# NODE_3_SCH.net
KiCad netlist of a schematic drawn in Altium Designer
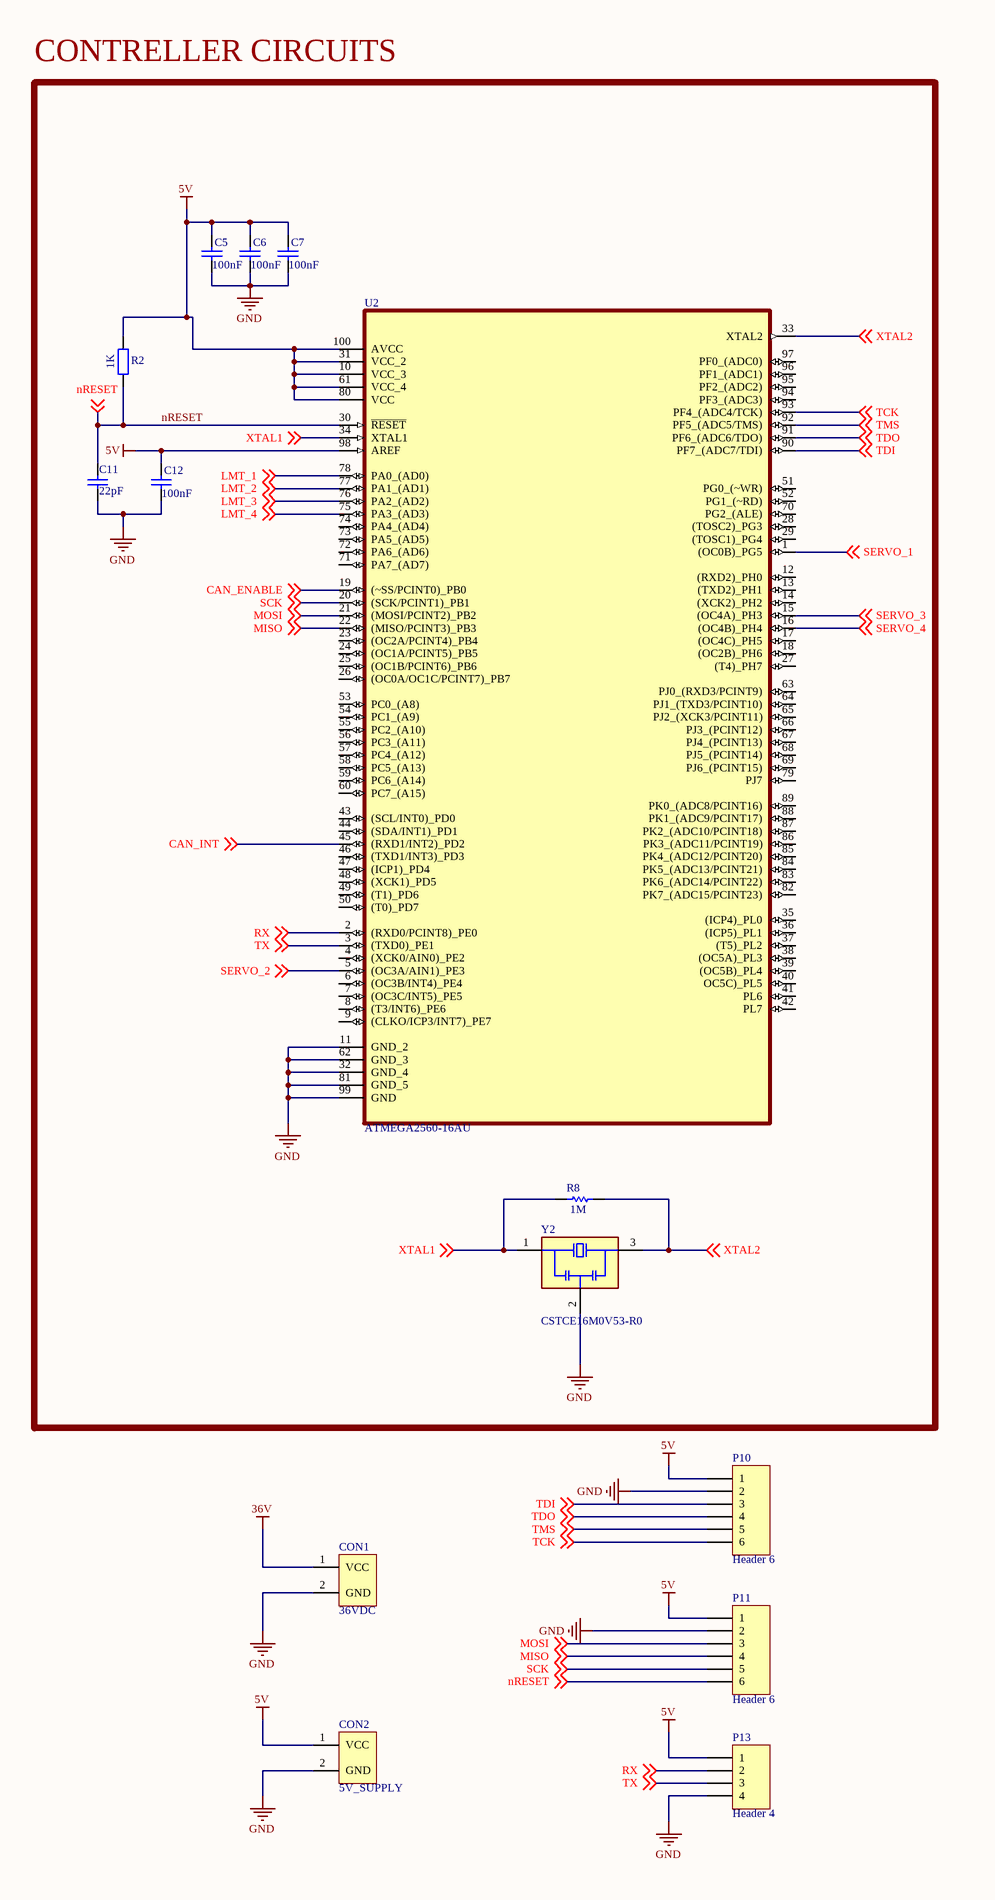
[diagram p0: NODE_3_SCH.SchDoc, left]
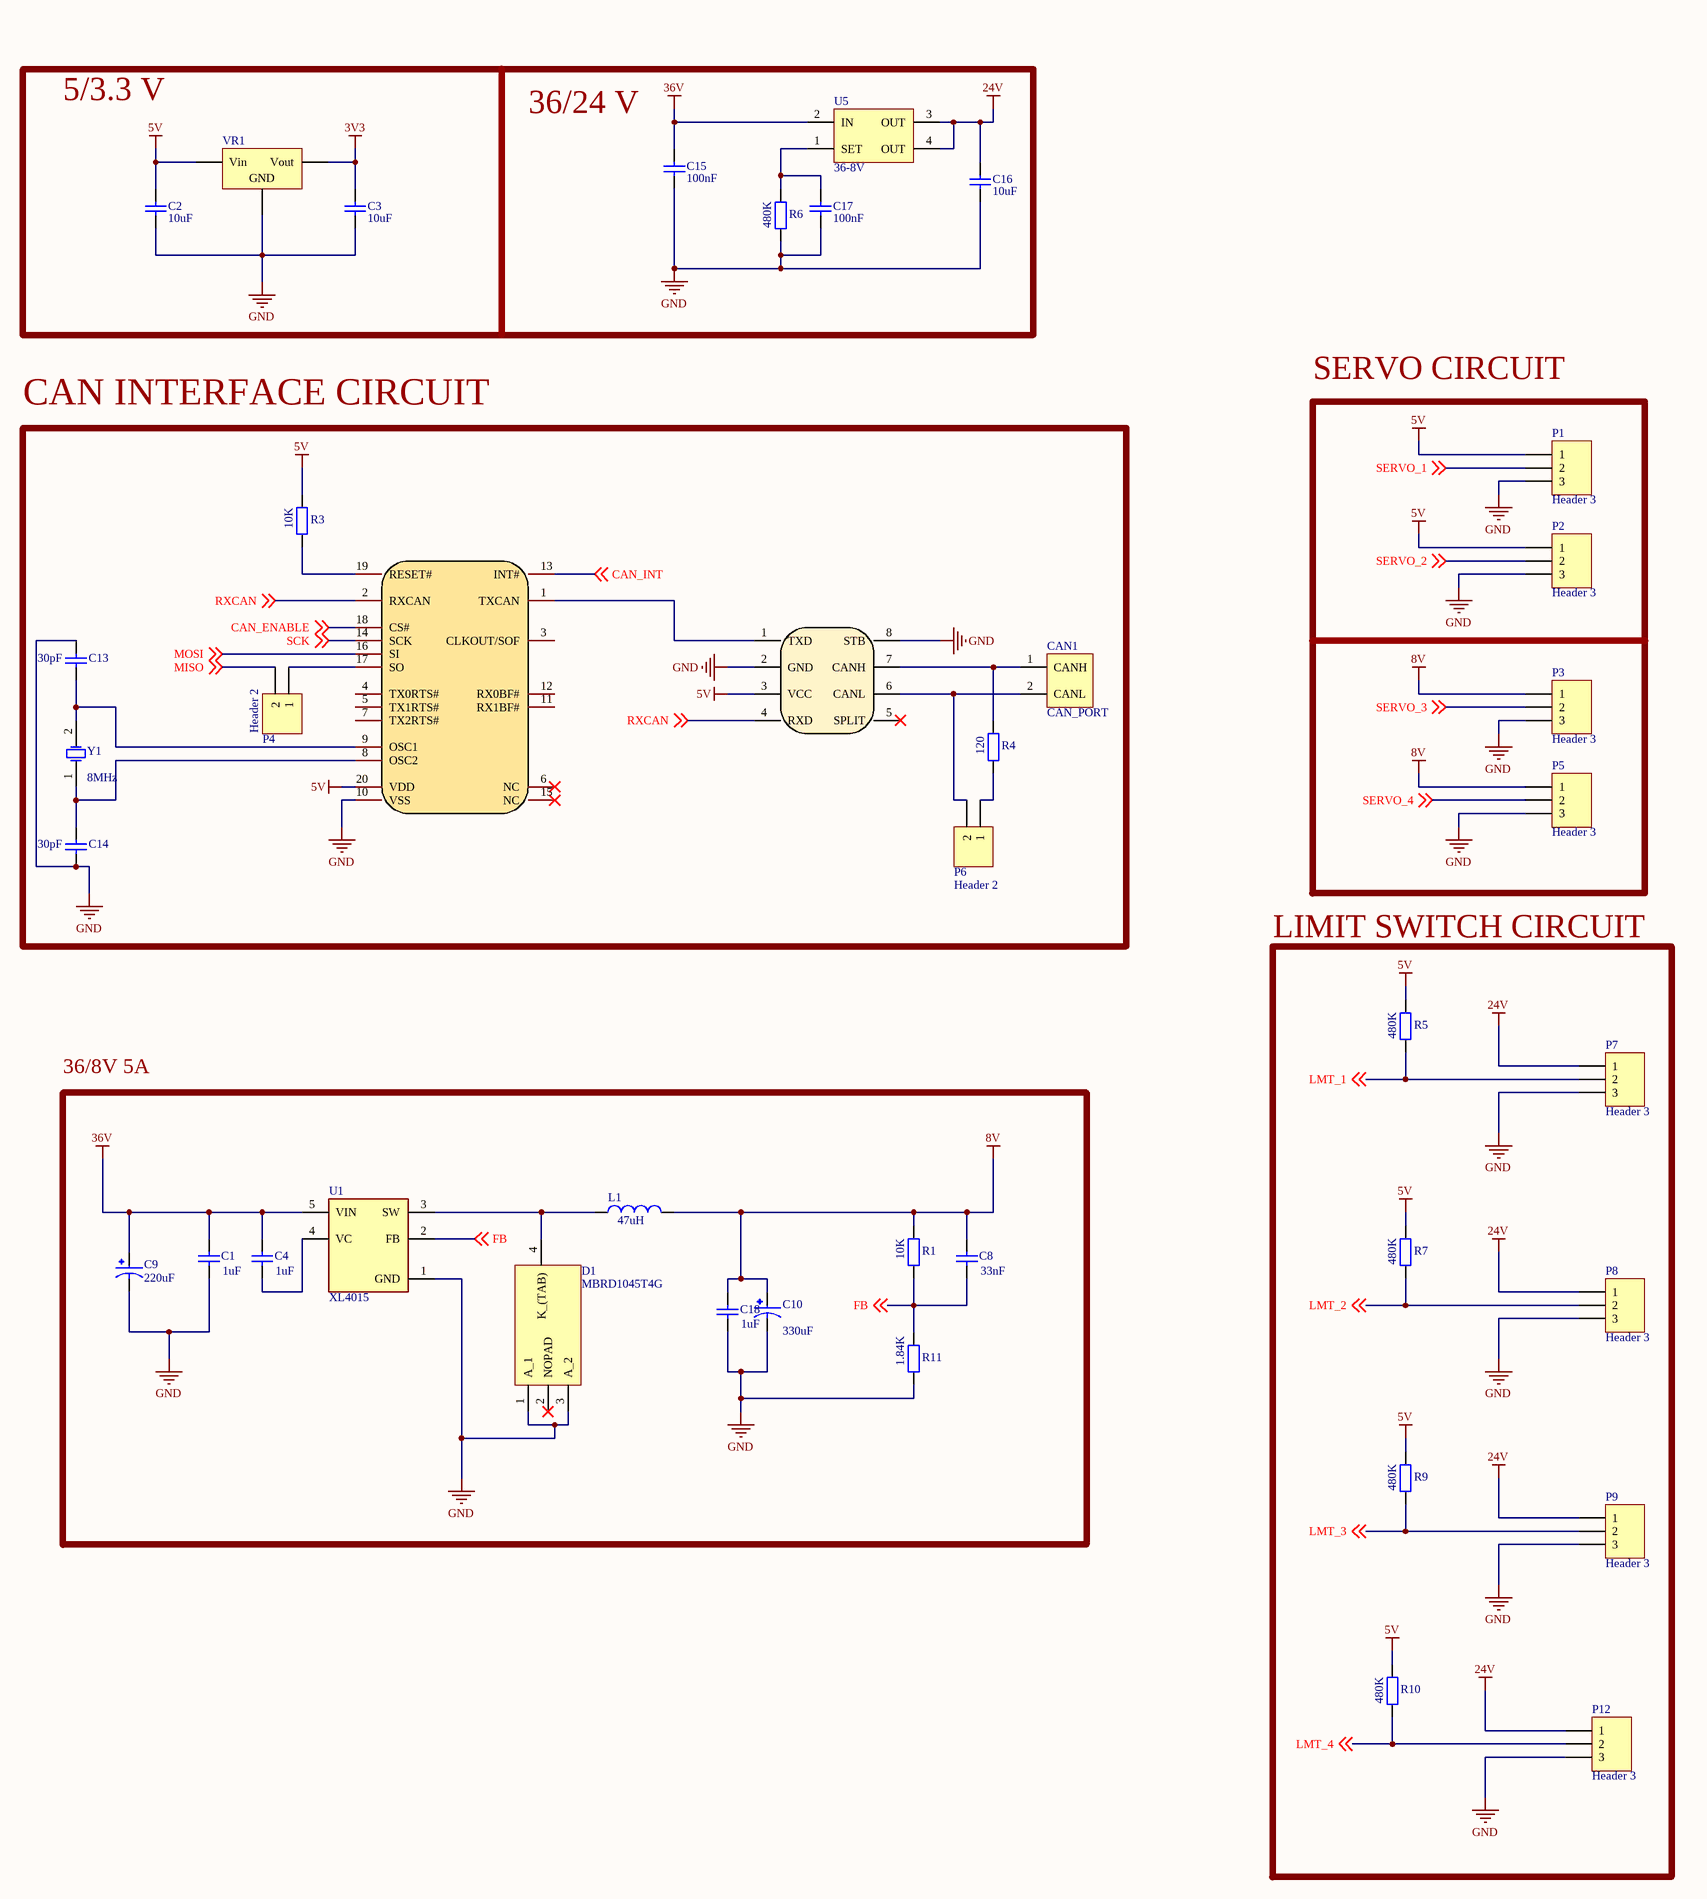
[diagram p1: NODE_3_SCH.SchDoc, right]

(export (version "E")
  (design (tool "Eeschema 10.0.6"))
  (components
    (comp (ref "C1")
      (value "1uF")
      (footprint "CAPC2012X135N")
      (description "Capacitor")
      (fields
        (field (name "PART NUMBER") "CL21B105KBFNNNE")
        (field (name "Comment") "Cap")
        (field (name "PUBLISHER") "Altium Limited")
      )
      (libsource (lib "Miscellaneous Devices") (part "Cap"))
    )
    (comp (ref "C2")
      (value "10uF")
      (footprint "CAPC2012X135N")
      (description "Capacitor")
      (fields
        (field (name "PART NUMBER") "CL21A106KOQNNNE")
        (field (name "Comment") "Cap")
        (field (name "PUBLISHER") "Altium Limited")
      )
      (libsource (lib "Miscellaneous Devices") (part "Cap"))
    )
    (comp (ref "C3")
      (value "10uF")
      (footprint "CAPC2012X135N")
      (description "Capacitor")
      (fields
        (field (name "PART NUMBER") "CL21A106KOQNNNE")
        (field (name "Comment") "Cap")
        (field (name "PUBLISHER") "Altium Limited")
      )
      (libsource (lib "Miscellaneous Devices") (part "Cap"))
    )
    (comp (ref "C4")
      (value "1uF")
      (footprint "CAPC2012X135N")
      (description "Capacitor")
      (fields
        (field (name "PART NUMBER") "CL21B105KBFNNNE")
        (field (name "Comment") "Cap")
        (field (name "PUBLISHER") "Altium Limited")
      )
      (libsource (lib "Miscellaneous Devices") (part "Cap"))
    )
    (comp (ref "C5")
      (value "100nF")
      (footprint "CAPC2012X135N")
      (description "Capacitor")
      (fields
        (field (name "PART NUMBER") "TCC0805X7R104M500DT")
        (field (name "Comment") "Cap")
        (field (name "PUBLISHER") "Altium Limited")
      )
      (libsource (lib "Miscellaneous Devices") (part "Cap"))
    )
    (comp (ref "C6")
      (value "100nF")
      (footprint "CAPC2012X135N")
      (description "Capacitor")
      (fields
        (field (name "PART NUMBER") "TCC0805X7R104M500DT")
        (field (name "Comment") "Cap")
        (field (name "PUBLISHER") "Altium Limited")
      )
      (libsource (lib "Miscellaneous Devices") (part "Cap"))
    )
    (comp (ref "C7")
      (value "100nF")
      (footprint "CAPC2012X135N")
      (description "Capacitor")
      (fields
        (field (name "PART NUMBER") "TCC0805X7R104M500DT")
        (field (name "Comment") "Cap")
        (field (name "PUBLISHER") "Altium Limited")
      )
      (libsource (lib "Miscellaneous Devices") (part "Cap"))
    )
    (comp (ref "C8")
      (value "33nF")
      (footprint "CAPC2012X135N")
      (description "Capacitor")
      (fields
        (field (name "PART NUMBER") "TCC0805X7R333M500DT")
        (field (name "Comment") "Cap")
        (field (name "PUBLISHER") "Altium Limited")
      )
      (libsource (lib "Miscellaneous Devices") (part "Cap"))
    )
    (comp (ref "C9")
      (value "220uF")
      (footprint "CAP_EEVTG1H221Q")
      (description "220ÂµF 50V Aluminum Electrolytic Capacitors Radial, Can - SMD 230mOhm @ 100kHz 2000 Hrs @ 125Â°C")
      (fields (field (name "MF") "Panasonic Electronic") (field (name "PART NUMBER") "EEV-TG1H221Q"))
      (libsource (lib "IOT_Library") (part "EEVTG1H221Q"))
    )
    (comp (ref "C10")
      (value "330uF")
      (footprint "CAP_EEEFN1E331V")
      (description "CAP ALUM 330UF 20% 25V SMD")
      (fields (field (name "MF") "Panasonic") (field (name "DIGI-KEY_PART_NUMBER") "10-EEE-FN1E331VTR-ND"))
      (libsource (lib "IOT_Library") (part "EEEFN1E331V"))
    )
    (comp (ref "C11")
      (value "22pF")
      (footprint "CAPC2012X135N")
      (description "Capacitor")
      (fields
        (field (name "PART NUMBER") "TCC0805COG220J500BT")
        (field (name "Comment") "Cap")
        (field (name "PUBLISHER") "Altium Limited")
      )
      (libsource (lib "Miscellaneous Devices") (part "Cap"))
    )
    (comp (ref "C12")
      (value "100nF")
      (footprint "CAPC2012X135N")
      (description "Capacitor")
      (fields
        (field (name "PART NUMBER") "TCC0805X7R104M500DT")
        (field (name "Comment") "Cap")
        (field (name "PUBLISHER") "Altium Limited")
      )
      (libsource (lib "Miscellaneous Devices") (part "Cap"))
    )
    (comp (ref "C13")
      (value "30pF")
      (footprint "CAPC2012X135N")
      (description "Capacitor")
      (fields
        (field (name "PART NUMBER") "TCC0805COG300J500BT")
        (field (name "Comment") "Cap")
        (field (name "PUBLISHER") "Altium Limited")
      )
      (libsource (lib "Miscellaneous Devices") (part "Cap"))
    )
    (comp (ref "C14")
      (value "30pF")
      (footprint "CAPC2012X135N")
      (description "Capacitor")
      (fields
        (field (name "PART NUMBER") "TCC0805COG300J500BT")
        (field (name "Comment") "Cap")
        (field (name "PUBLISHER") "Altium Limited")
      )
      (libsource (lib "Miscellaneous Devices") (part "Cap"))
    )
    (comp (ref "C15")
      (value "100nF")
      (footprint "CAPC2012X135N")
      (description "Capacitor")
      (fields
        (field (name "PART NUMBER") "TCC0805X7R104M500DT")
        (field (name "Comment") "Cap")
        (field (name "PUBLISHER") "Altium Limited")
      )
      (libsource (lib "Miscellaneous Devices") (part "Cap"))
    )
    (comp (ref "C16")
      (value "10uF")
      (footprint "CAPC2012X135N")
      (description "Capacitor")
      (fields
        (field (name "PART NUMBER") "CL21A106KOQNNNE")
        (field (name "Comment") "Cap")
        (field (name "PUBLISHER") "Altium Limited")
      )
      (libsource (lib "Miscellaneous Devices") (part "Cap"))
    )
    (comp (ref "C17")
      (value "100nF")
      (footprint "CAPC2012X135N")
      (description "Capacitor")
      (fields
        (field (name "PART NUMBER") "TCC0805X7R104M500DT")
        (field (name "Comment") "Cap")
        (field (name "PUBLISHER") "Altium Limited")
      )
      (libsource (lib "Miscellaneous Devices") (part "Cap"))
    )
    (comp (ref "C18")
      (value "1uF")
      (footprint "CAPC2012X135N")
      (description "Capacitor")
      (fields
        (field (name "PART NUMBER") "CL21B105KBFNNNE")
        (field (name "Comment") "Cap")
        (field (name "PUBLISHER") "Altium Limited")
      )
      (libsource (lib "Miscellaneous Devices") (part "Cap"))
    )
    (comp (ref "CAN1")
      (value "CAN_PORT")
      (footprint "12V_CON")
      (fields (field (name "PART NUMBER") "MX126-5.0-02P-GN01-Cu-S-A"))
      (libsource (lib "IOT_Library") (part "2PIN_CON_1"))
    )
    (comp (ref "CON1")
      (value "36VDC")
      (footprint "12V_CON")
      (fields (field (name "PART NUMBER") "MX126-5.0-02P-GN01-Cu-S-A"))
      (libsource (lib "IOT_Library") (part "2PIN_CON_2"))
    )
    (comp (ref "CON2")
      (value "5V_SUPPLY")
      (footprint "12V_CON")
      (fields (field (name "PART NUMBER") "MX126-5.0-02P-GN01-Cu-S-A"))
      (libsource (lib "IOT_Library") (part "2PIN_CON"))
    )
    (comp (ref "D1")
      (value "MBRD1045T4G")
      (footprint "TO229P990X238-4N")
      (description "Diode Schottky 45V 10A Surface Mount DPAK")
      (fields (field (name "MF") "ON Semiconductor"))
      (libsource (lib "IOT_Library") (part "MBRD1045T4G"))
    )
    (comp (ref "L1")
      (value "47uH")
      (footprint "IND_MWSA1206S_SNL")
      (description "Inductor")
      (fields (field (name "PART NUMBER") "MWSA1206S-470MT") (field (name "PUBLISHER") "Altium Limited"))
      (libsource (lib "Miscellaneous Devices") (part "Inductor"))
    )
    (comp (ref "P1")
      (value "Header 3")
      (footprint "3PIN_H")
      (description "Header, 3-Pin")
      (fields (field (name "PART NUMBER") "DB125-3.81-3P-BK-S") (field (name "PUBLISHER") "Altium Limited"))
      (libsource (lib "Miscellaneous Connectors") (part "Header 3"))
    )
    (comp (ref "P2")
      (value "Header 3")
      (footprint "3PIN_H")
      (description "Header, 3-Pin")
      (fields (field (name "PART NUMBER") "DB125-3.81-3P-BK-S") (field (name "PUBLISHER") "Altium Limited"))
      (libsource (lib "Miscellaneous Connectors") (part "Header 3"))
    )
    (comp (ref "P3")
      (value "Header 3")
      (footprint "3PIN_H")
      (description "Header, 3-Pin")
      (fields (field (name "PART NUMBER") "DB125-3.81-3P-BK-S") (field (name "PUBLISHER") "Altium Limited"))
      (libsource (lib "Miscellaneous Connectors") (part "Header 3"))
    )
    (comp (ref "P4")
      (value "Header 2")
      (footprint "SAMTEC_TS-102-G-A")
      (description "Header, 2-Pin")
      (fields (field (name "PART NUMBER") "PH-01078") (field (name "PUBLISHER") "Altium Limited"))
      (libsource (lib "Miscellaneous Connectors") (part "Header 2"))
    )
    (comp (ref "P5")
      (value "Header 3")
      (footprint "3PIN_H")
      (description "Header, 3-Pin")
      (fields (field (name "PART NUMBER") "DB125-3.81-3P-BK-S") (field (name "PUBLISHER") "Altium Limited"))
      (libsource (lib "Miscellaneous Connectors") (part "Header 3"))
    )
    (comp (ref "P6")
      (value "Header 2")
      (footprint "SAMTEC_TS-102-G-A")
      (description "Header, 2-Pin")
      (fields (field (name "PART NUMBER") "PH-01078") (field (name "PUBLISHER") "Altium Limited"))
      (libsource (lib "Miscellaneous Connectors") (part "Header 2"))
    )
    (comp (ref "P7")
      (value "Header 3")
      (footprint "3PIN_H")
      (description "Header, 3-Pin")
      (fields (field (name "PART NUMBER") "DB125-3.81-3P-BK-S") (field (name "PUBLISHER") "Altium Limited"))
      (libsource (lib "Miscellaneous Connectors") (part "Header 3"))
    )
    (comp (ref "P8")
      (value "Header 3")
      (footprint "3PIN_H")
      (description "Header, 3-Pin")
      (fields (field (name "PART NUMBER") "DB125-3.81-3P-BK-S") (field (name "PUBLISHER") "Altium Limited"))
      (libsource (lib "Miscellaneous Connectors") (part "Header 3"))
    )
    (comp (ref "P9")
      (value "Header 3")
      (footprint "3PIN_H")
      (description "Header, 3-Pin")
      (fields (field (name "PART NUMBER") "DB125-3.81-3P-BK-S") (field (name "PUBLISHER") "Altium Limited"))
      (libsource (lib "Miscellaneous Connectors") (part "Header 3"))
    )
    (comp (ref "P10")
      (value "Header 6")
      (footprint "HDR1X6")
      (description "Header, 6-Pin")
      (fields (field (name "PART NUMBER") "HB-PH3-25414PB2GOP") (field (name "PUBLISHER") "Altium Limited"))
      (libsource (lib "Miscellaneous Connectors") (part "Header 6"))
    )
    (comp (ref "P11")
      (value "Header 6")
      (footprint "HDR1X6")
      (description "Header, 6-Pin")
      (fields (field (name "PART NUMBER") "HB-PH3-25414PB2GOP") (field (name "PUBLISHER") "Altium Limited"))
      (libsource (lib "Miscellaneous Connectors") (part "Header 6"))
    )
    (comp (ref "P12")
      (value "Header 3")
      (footprint "3PIN_H")
      (description "Header, 3-Pin")
      (fields (field (name "PART NUMBER") "DB125-3.81-3P-BK-S") (field (name "PUBLISHER") "Altium Limited"))
      (libsource (lib "Miscellaneous Connectors") (part "Header 3"))
    )
    (comp (ref "P13")
      (value "Header 4")
      (footprint "HDR1X4")
      (description "Header, 4-Pin")
      (fields (field (name "PART NUMBER") "P125-1106A0BS116A1") (field (name "PUBLISHER") "Altium Limited"))
      (libsource (lib "Miscellaneous Connectors") (part "Header 4"))
    )
    (comp (ref "R1")
      (value "10K")
      (footprint "RESC2013X06N")
      (description "Resistor")
      (fields
        (field (name "PART NUMBER") "RC0805JR-0710KL")
        (field (name "Comment") "Res2")
        (field (name "PUBLISHER") "Altium Limited")
      )
      (libsource (lib "Miscellaneous Devices") (part "Res2"))
    )
    (comp (ref "R2")
      (value "1K")
      (footprint "RESC2013X06N")
      (description "Resistor")
      (fields
        (field (name "PART NUMBER") "0805W8J0102T5E")
        (field (name "Comment") "Res2")
        (field (name "PUBLISHER") "Altium Limited")
      )
      (libsource (lib "Miscellaneous Devices") (part "Res2"))
    )
    (comp (ref "R3")
      (value "10K")
      (footprint "RESC2013X06N")
      (description "Resistor")
      (fields
        (field (name "PART NUMBER") "RC0805JR-0710KL")
        (field (name "Comment") "Res2")
        (field (name "PUBLISHER") "Altium Limited")
      )
      (libsource (lib "Miscellaneous Devices") (part "Res2"))
    )
    (comp (ref "R4")
      (value "120")
      (footprint "CRCW1206120RFKEAHP")
      (description "Resistor")
      (fields
        (field (name "PART NUMBER") "CRCW1206120RFKEAHP")
        (field (name "Comment") "Res2")
        (field (name "PUBLISHER") "Altium Limited")
      )
      (libsource (lib "Miscellaneous Devices") (part "Res2"))
    )
    (comp (ref "R5")
      (value "480K")
      (footprint "CRCW1206120RFKEAHP")
      (description "Resistor")
      (fields
        (field (name "PART NUMBER") "1206W4J0484T5E")
        (field (name "Comment") "Res2")
        (field (name "PUBLISHER") "Altium Limited")
      )
      (libsource (lib "Miscellaneous Devices") (part "Res2"))
    )
    (comp (ref "R6")
      (value "480K")
      (footprint "CRCW1206120RFKEAHP")
      (description "Resistor")
      (fields
        (field (name "PART NUMBER") "1206W4J0484T5E")
        (field (name "Comment") "Res2")
        (field (name "PUBLISHER") "Altium Limited")
      )
      (libsource (lib "Miscellaneous Devices") (part "Res2"))
    )
    (comp (ref "R7")
      (value "480K")
      (footprint "CRCW1206120RFKEAHP")
      (description "Resistor")
      (fields
        (field (name "PART NUMBER") "1206W4J0484T5E")
        (field (name "Comment") "Res2")
        (field (name "PUBLISHER") "Altium Limited")
      )
      (libsource (lib "Miscellaneous Devices") (part "Res2"))
    )
    (comp (ref "R8")
      (value "1M")
      (footprint "RESC2013X06N")
      (description "Resistor")
      (fields
        (field (name "PART NUMBER") "RC0805JR-071KL")
        (field (name "Comment") "Res1")
        (field (name "PUBLISHER") "Altium Limited")
      )
      (libsource (lib "Miscellaneous Devices") (part "Res1"))
    )
    (comp (ref "R9")
      (value "480K")
      (footprint "CRCW1206120RFKEAHP")
      (description "Resistor")
      (fields
        (field (name "PART NUMBER") "1206W4J0484T5E")
        (field (name "Comment") "Res2")
        (field (name "PUBLISHER") "Altium Limited")
      )
      (libsource (lib "Miscellaneous Devices") (part "Res2"))
    )
    (comp (ref "R10")
      (value "480K")
      (footprint "CRCW1206120RFKEAHP")
      (description "Resistor")
      (fields
        (field (name "PART NUMBER") "1206W4J0484T5E")
        (field (name "Comment") "Res2")
        (field (name "PUBLISHER") "Altium Limited")
      )
      (libsource (lib "Miscellaneous Devices") (part "Res2"))
    )
    (comp (ref "R11")
      (value "1.84K")
      (footprint "0603_STANDARD")
      (description "Resistor")
      (fields
        (field (name "PART NUMBER") "RT0603BRD071K84L")
        (field (name "Comment") "Res2")
        (field (name "PUBLISHER") "Altium Limited")
      )
      (libsource (lib "Miscellaneous Devices") (part "Res2"))
    )
    (comp (ref "U1")
      (value "XL4015")
      (footprint "CONV_XL4015")
      (description "5A 180KHz 36V Buck DC to DC Converter")
      (fields (field (name "PART NUMBER") "XL4015E1"))
      (libsource (lib "IOT_Library") (part "XL4015"))
    )
    (comp (ref "U2")
      (value "ATMEGA2560-16AU")
      (footprint "QFP50P1600X1600X120-100N")
      (description "AVR AVRÂ® ATmega Microcontroller IC 8-Bit 16MHz 256KB (128K x 16) FLASH 100-TQFP (14x14)")
      (fields (field (name "MF") "Microchip"))
      (libsource (lib "IOT_Library") (part "ATMEGA2560-16AU"))
    )
    (comp (ref "U3")
      (value "TJA1050DRG")
      (footprint "SOP-8_L4.9-W3.9-P1.27-LS6.0-BL - duplicate")
      (fields (field (name "MANUFACTURER") "HGC(深圳汉芯)"))
      (libsource (lib "IOT_Library") (part "TJA1050DRG"))
    )
    (comp (ref "U4")
      (value "MCP2515T-I/ST")
      (footprint "TSSOP-20_L6.5-W4.4-P0.65-LS6.4-BL")
      (fields (field (name "MANUFACTURER") "MICROCHIP(美国微芯)"))
      (libsource (lib "IOT_Library") (part "MCP2515T-I/ST"))
    )
    (comp (ref "U5")
      (value "36-8V")
      (footprint "SOT-223-3_L6.5-W3.4-P2.30-LS7.0-BR")
      (description "LDO Regulator Pos 0V to 34.5V 0.8A Automotive 4-Pin(3+Tab) SOT-223 Tube")
      (fields
        (field (name "MANUFACTURER") "Analog Devices / Linear Technology")
        (field (name "PART NUMBER") "LT3088MPST#PBF")
      )
      (libsource (lib "IOT_Library") (part "LT3088MPST#PBF"))
    )
    (comp (ref "VR1")
      (value "5-3.3V")
      (footprint "TO-252-2_L6.6-W6.1-P4.57-LS9.9-BR-CW")
      (description "Voltage Regulator")
      (fields (field (name "PART NUMBER") "AP7363-33D-13") (field (name "PUBLISHER") "Altium Limited"))
      (libsource (lib "Miscellaneous Devices") (part "Volt Reg"))
    )
    (comp (ref "Y1")
      (value "8MHz")
      (footprint "CRYSTAL-SMD_L7.4-W4.0-LS8.0")
      (description "Crystal Oscillator")
      (fields
        (field (name "PART NUMBER") "S47SMD8.000M12PF20R30B3")
        (field (name "Comment") "XTAL")
        (field (name "PUBLISHER") "Altium Limited")
      )
      (libsource (lib "Miscellaneous Devices") (part "XTAL"))
    )
    (comp (ref "Y2")
      (value "CSTCE16M0V53-R0")
      (footprint "OSC_CSTCE16M0V53-R0")
      (description "16 MHz Ceramic Resonator Built in Capacitor 15 pF Â±0.3% -20Â°C ~ 80Â°C Surface Mount")
      (fields (field (name "MF") "Murata"))
      (libsource (lib "IOT_Library") (part "CSTCE16M0V53-R0"))
    )
  )
  (nets
    (net (code "1") (name "3V3") (class "Default")
      (node (ref "C3") (pin "2") (pinfunction "2_2") (pintype "passive"))
      (node (ref "VR1") (pin "3") (pinfunction "Vout_3") (pintype "passive"))
    )
    (net (code "2") (name "5V") (class "Default")
      (node (ref "C12") (pin "1") (pinfunction "1_1") (pintype "passive"))
      (node (ref "C2") (pin "2") (pinfunction "2_2") (pintype "passive"))
      (node (ref "C5") (pin "1") (pinfunction "1_1") (pintype "passive"))
      (node (ref "C6") (pin "1") (pinfunction "1_1") (pintype "passive"))
      (node (ref "C7") (pin "1") (pinfunction "1_1") (pintype "passive"))
      (node (ref "CON2") (pin "1") (pinfunction "VCC_1") (pintype "passive"))
      (node (ref "P1") (pin "1") (pinfunction "1_1") (pintype "passive"))
      (node (ref "P10") (pin "1") (pinfunction "1_1") (pintype "passive"))
      (node (ref "P11") (pin "1") (pinfunction "1_1") (pintype "passive"))
      (node (ref "P13") (pin "1") (pinfunction "1_1") (pintype "passive"))
      (node (ref "P2") (pin "1") (pinfunction "1_1") (pintype "passive"))
      (node (ref "R10") (pin "2") (pinfunction "2_2") (pintype "passive"))
      (node (ref "R2") (pin "2") (pinfunction "2_2") (pintype "passive"))
      (node (ref "R3") (pin "2") (pinfunction "2_2") (pintype "passive"))
      (node (ref "R5") (pin "2") (pinfunction "2_2") (pintype "passive"))
      (node (ref "R7") (pin "2") (pinfunction "2_2") (pintype "passive"))
      (node (ref "R9") (pin "2") (pinfunction "2_2") (pintype "passive"))
      (node (ref "U2") (pin "10") (pinfunction "VCC_3_10") (pintype "power_in"))
      (node (ref "U2") (pin "100") (pinfunction "AVCC_100") (pintype "power_in"))
      (node (ref "U2") (pin "31") (pinfunction "VCC_2_31") (pintype "power_in"))
      (node (ref "U2") (pin "61") (pinfunction "VCC_4_61") (pintype "power_in"))
      (node (ref "U2") (pin "80") (pinfunction "VCC_80") (pintype "power_in"))
      (node (ref "U2") (pin "98") (pinfunction "AREF_98") (pintype "input"))
      (node (ref "U3") (pin "3") (pinfunction "VCC_3") (pintype "passive"))
      (node (ref "U4") (pin "20") (pinfunction "VDD_20") (pintype "passive"))
      (node (ref "VR1") (pin "1") (pinfunction "Vin_1") (pintype "passive"))
    )
    (net (code "3") (name "8V") (class "Default")
      (node (ref "C10") (pin "1") (pinfunction "1_1") (pintype "passive"))
      (node (ref "C18") (pin "1") (pinfunction "1_1") (pintype "passive"))
      (node (ref "C8") (pin "1") (pinfunction "1_1") (pintype "passive"))
      (node (ref "L1") (pin "2") (pinfunction "2_2") (pintype "passive"))
      (node (ref "P3") (pin "1") (pinfunction "1_1") (pintype "passive"))
      (node (ref "P5") (pin "1") (pinfunction "1_1") (pintype "passive"))
      (node (ref "R1") (pin "2") (pinfunction "2_2") (pintype "passive"))
    )
    (net (code "4") (name "24V") (class "Default")
      (node (ref "C16") (pin "2") (pinfunction "2_2") (pintype "passive"))
      (node (ref "P12") (pin "1") (pinfunction "1_1") (pintype "passive"))
      (node (ref "P7") (pin "1") (pinfunction "1_1") (pintype "passive"))
      (node (ref "P8") (pin "1") (pinfunction "1_1") (pintype "passive"))
      (node (ref "P9") (pin "1") (pinfunction "1_1") (pintype "passive"))
      (node (ref "U5") (pin "3") (pinfunction "OUT_3") (pintype "passive"))
      (node (ref "U5") (pin "4") (pinfunction "OUT_4") (pintype "passive"))
    )
    (net (code "5") (name "36V") (class "Default")
      (node (ref "C1") (pin "1") (pinfunction "1_1") (pintype "passive"))
      (node (ref "C15") (pin "2") (pinfunction "2_2") (pintype "passive"))
      (node (ref "C4") (pin "1") (pinfunction "1_1") (pintype "passive"))
      (node (ref "C9") (pin "1") (pinfunction "1_1") (pintype "passive"))
      (node (ref "CON1") (pin "1") (pinfunction "VCC_1") (pintype "passive"))
      (node (ref "U1") (pin "5") (pinfunction "VIN_5") (pintype "passive"))
      (node (ref "U5") (pin "2") (pinfunction "IN_2") (pintype "passive"))
    )
    (net (code "6") (name "CAN_ENABLE") (class "Default")
      (node (ref "U2") (pin "19") (pinfunction "(~SS/PCINT0)_PB0_19") (pintype "bidirectional"))
      (node (ref "U4") (pin "18") (pinfunction "CS#_18") (pintype "passive"))
    )
    (net (code "7") (name "CAN_INT") (class "Default")
      (node (ref "U2") (pin "45") (pinfunction "(RXD1/INT2)_PD2_45") (pintype "bidirectional"))
      (node (ref "U4") (pin "13") (pinfunction "INT#_13") (pintype "passive"))
    )
    (net (code "8") (name "FB") (class "Default")
      (node (ref "C8") (pin "2") (pinfunction "2_2") (pintype "passive"))
      (node (ref "R1") (pin "1") (pinfunction "1_1") (pintype "passive"))
      (node (ref "R11") (pin "2") (pinfunction "2_2") (pintype "passive"))
      (node (ref "U1") (pin "2") (pinfunction "FB_2") (pintype "passive"))
    )
    (net (code "9") (name "GND") (class "Default")
      (node (ref "C1") (pin "2") (pinfunction "2_2") (pintype "passive"))
      (node (ref "C10") (pin "2") (pinfunction "2_2") (pintype "passive"))
      (node (ref "C11") (pin "2") (pinfunction "2_2") (pintype "passive"))
      (node (ref "C12") (pin "2") (pinfunction "2_2") (pintype "passive"))
      (node (ref "C13") (pin "1") (pinfunction "1_1") (pintype "passive"))
      (node (ref "C14") (pin "2") (pinfunction "2_2") (pintype "passive"))
      (node (ref "C15") (pin "1") (pinfunction "1_1") (pintype "passive"))
      (node (ref "C16") (pin "1") (pinfunction "1_1") (pintype "passive"))
      (node (ref "C17") (pin "1") (pinfunction "1_1") (pintype "passive"))
      (node (ref "C18") (pin "2") (pinfunction "2_2") (pintype "passive"))
      (node (ref "C2") (pin "1") (pinfunction "1_1") (pintype "passive"))
      (node (ref "C3") (pin "1") (pinfunction "1_1") (pintype "passive"))
      (node (ref "C5") (pin "2") (pinfunction "2_2") (pintype "passive"))
      (node (ref "C6") (pin "2") (pinfunction "2_2") (pintype "passive"))
      (node (ref "C7") (pin "2") (pinfunction "2_2") (pintype "passive"))
      (node (ref "C9") (pin "2") (pinfunction "2_2") (pintype "passive"))
      (node (ref "CON1") (pin "2") (pinfunction "GND_2") (pintype "passive"))
      (node (ref "CON2") (pin "2") (pinfunction "GND_2") (pintype "passive"))
      (node (ref "D1") (pin "1") (pinfunction "A_1_1") (pintype "passive"))
      (node (ref "D1") (pin "3") (pinfunction "A_2_3") (pintype "passive"))
      (node (ref "P1") (pin "3") (pinfunction "3_3") (pintype "passive"))
      (node (ref "P10") (pin "2") (pinfunction "2_2") (pintype "passive"))
      (node (ref "P11") (pin "2") (pinfunction "2_2") (pintype "passive"))
      (node (ref "P12") (pin "3") (pinfunction "3_3") (pintype "passive"))
      (node (ref "P13") (pin "4") (pinfunction "4_4") (pintype "passive"))
      (node (ref "P2") (pin "3") (pinfunction "3_3") (pintype "passive"))
      (node (ref "P3") (pin "3") (pinfunction "3_3") (pintype "passive"))
      (node (ref "P5") (pin "3") (pinfunction "3_3") (pintype "passive"))
      (node (ref "P7") (pin "3") (pinfunction "3_3") (pintype "passive"))
      (node (ref "P8") (pin "3") (pinfunction "3_3") (pintype "passive"))
      (node (ref "P9") (pin "3") (pinfunction "3_3") (pintype "passive"))
      (node (ref "R11") (pin "1") (pinfunction "1_1") (pintype "passive"))
      (node (ref "R6") (pin "1") (pinfunction "1_1") (pintype "passive"))
      (node (ref "U1") (pin "1") (pinfunction "GND_1") (pintype "power_in"))
      (node (ref "U2") (pin "11") (pinfunction "GND_2_11") (pintype "passive"))
      (node (ref "U2") (pin "32") (pinfunction "GND_4_32") (pintype "passive"))
      (node (ref "U2") (pin "62") (pinfunction "GND_3_62") (pintype "passive"))
      (node (ref "U2") (pin "81") (pinfunction "GND_5_81") (pintype "passive"))
      (node (ref "U2") (pin "99") (pinfunction "GND_99") (pintype "passive"))
      (node (ref "U3") (pin "2") (pinfunction "GND_2") (pintype "passive"))
      (node (ref "U3") (pin "8") (pinfunction "STB_8") (pintype "passive"))
      (node (ref "U4") (pin "10") (pinfunction "VSS_10") (pintype "passive"))
      (node (ref "VR1") (pin "2") (pinfunction "GND_2") (pintype "passive"))
      (node (ref "Y2") (pin "2") (pinfunction "GND_2") (pintype "power_in"))
    )
    (net (code "10") (name "LMT_1") (class "Default")
      (node (ref "P7") (pin "2") (pinfunction "2_2") (pintype "passive"))
      (node (ref "R5") (pin "1") (pinfunction "1_1") (pintype "passive"))
      (node (ref "U2") (pin "78") (pinfunction "PA0_(AD0)_78") (pintype "bidirectional"))
    )
    (net (code "11") (name "LMT_2") (class "Default")
      (node (ref "P8") (pin "2") (pinfunction "2_2") (pintype "passive"))
      (node (ref "R7") (pin "1") (pinfunction "1_1") (pintype "passive"))
      (node (ref "U2") (pin "77") (pinfunction "PA1_(AD1)_77") (pintype "bidirectional"))
    )
    (net (code "12") (name "LMT_3") (class "Default")
      (node (ref "P9") (pin "2") (pinfunction "2_2") (pintype "passive"))
      (node (ref "R9") (pin "1") (pinfunction "1_1") (pintype "passive"))
      (node (ref "U2") (pin "76") (pinfunction "PA2_(AD2)_76") (pintype "bidirectional"))
    )
    (net (code "13") (name "LMT_4") (class "Default")
      (node (ref "P12") (pin "2") (pinfunction "2_2") (pintype "passive"))
      (node (ref "R10") (pin "1") (pinfunction "1_1") (pintype "passive"))
      (node (ref "U2") (pin "75") (pinfunction "PA3_(AD3)_75") (pintype "bidirectional"))
    )
    (net (code "14") (name "MISO") (class "Default")
      (node (ref "P11") (pin "4") (pinfunction "4_4") (pintype "passive"))
      (node (ref "P4") (pin "2") (pinfunction "2_2") (pintype "passive"))
      (node (ref "U2") (pin "22") (pinfunction "(MISO/PCINT3)_PB3_22") (pintype "bidirectional"))
    )
    (net (code "15") (name "MOSI") (class "Default")
      (node (ref "P11") (pin "3") (pinfunction "3_3") (pintype "passive"))
      (node (ref "U2") (pin "21") (pinfunction "(MOSI/PCINT2)_PB2_21") (pintype "bidirectional"))
      (node (ref "U4") (pin "16") (pinfunction "SI_16") (pintype "passive"))
    )
    (net (code "16") (name "Net-(CAN1-CANH)") (class "Default")
      (node (ref "CAN1") (pin "1") (pinfunction "CANH_1") (pintype "passive"))
      (node (ref "R4") (pin "2") (pinfunction "2_2") (pintype "passive"))
      (node (ref "U3") (pin "7") (pinfunction "CANH_7") (pintype "passive"))
    )
    (net (code "17") (name "Net-(CAN1-CANL)") (class "Default")
      (node (ref "CAN1") (pin "2") (pinfunction "CANL_2") (pintype "passive"))
      (node (ref "P6") (pin "2") (pinfunction "2_2") (pintype "passive"))
      (node (ref "U3") (pin "6") (pinfunction "CANL_6") (pintype "passive"))
    )
    (net (code "18") (name "Net-(D1-K_(TAB))") (class "Default")
      (node (ref "D1") (pin "4") (pinfunction "K_(TAB)_4") (pintype "passive"))
      (node (ref "L1") (pin "1") (pinfunction "1_1") (pintype "passive"))
      (node (ref "U1") (pin "3") (pinfunction "SW_3") (pintype "passive"))
    )
    (net (code "19") (name "Net-(P6-Pad1)") (class "Default")
      (node (ref "P6") (pin "1") (pinfunction "1_1") (pintype "passive"))
      (node (ref "R4") (pin "1") (pinfunction "1_1") (pintype "passive"))
    )
    (net (code "20") (name "Net-(U1-VC)") (class "Default")
      (node (ref "C4") (pin "2") (pinfunction "2_2") (pintype "passive"))
      (node (ref "U1") (pin "4") (pinfunction "VC_4") (pintype "passive"))
    )
    (net (code "21") (name "Net-(U3-TXD)") (class "Default")
      (node (ref "U3") (pin "1") (pinfunction "TXD_1") (pintype "passive"))
      (node (ref "U4") (pin "1") (pinfunction "TXCAN_1") (pintype "passive"))
    )
    (net (code "22") (name "Net-(U4-OSC1)") (class "Default")
      (node (ref "C13") (pin "2") (pinfunction "2_2") (pintype "passive"))
      (node (ref "U4") (pin "9") (pinfunction "OSC1_9") (pintype "passive"))
      (node (ref "Y1") (pin "2") (pinfunction "OSC2_2") (pintype "passive"))
    )
    (net (code "23") (name "Net-(U4-OSC2)") (class "Default")
      (node (ref "C14") (pin "1") (pinfunction "1_1") (pintype "passive"))
      (node (ref "U4") (pin "8") (pinfunction "OSC2_8") (pintype "passive"))
      (node (ref "Y1") (pin "1") (pinfunction "OSC1_1") (pintype "passive"))
    )
    (net (code "24") (name "Net-(U4-RESET#)") (class "Default")
      (node (ref "R3") (pin "1") (pinfunction "1_1") (pintype "passive"))
      (node (ref "U4") (pin "19") (pinfunction "RESET#_19") (pintype "passive"))
    )
    (net (code "25") (name "Net-(U4-SO)") (class "Default")
      (node (ref "P4") (pin "1") (pinfunction "1_1") (pintype "passive"))
      (node (ref "U4") (pin "17") (pinfunction "SO_17") (pintype "passive"))
    )
    (net (code "26") (name "Net-(U5-SET)") (class "Default")
      (node (ref "C17") (pin "2") (pinfunction "2_2") (pintype "passive"))
      (node (ref "R6") (pin "2") (pinfunction "2_2") (pintype "passive"))
      (node (ref "U5") (pin "1") (pinfunction "SET_1") (pintype "passive"))
    )
    (net (code "27") (name "RX") (class "Default")
      (node (ref "P13") (pin "2") (pinfunction "2_2") (pintype "passive"))
      (node (ref "U2") (pin "2") (pinfunction "(RXD0/PCINT8)_PE0_2") (pintype "bidirectional"))
    )
    (net (code "28") (name "RXCAN") (class "Default")
      (node (ref "U3") (pin "4") (pinfunction "RXD_4") (pintype "passive"))
      (node (ref "U4") (pin "2") (pinfunction "RXCAN_2") (pintype "passive"))
    )
    (net (code "29") (name "SCK") (class "Default")
      (node (ref "P11") (pin "5") (pinfunction "5_5") (pintype "passive"))
      (node (ref "U2") (pin "20") (pinfunction "(SCK/PCINT1)_PB1_20") (pintype "bidirectional"))
      (node (ref "U4") (pin "14") (pinfunction "SCK_14") (pintype "passive"))
    )
    (net (code "30") (name "SERVO_1") (class "Default")
      (node (ref "P1") (pin "2") (pinfunction "2_2") (pintype "passive"))
      (node (ref "U2") (pin "1") (pinfunction "(OC0B)_PG5_1") (pintype "bidirectional"))
    )
    (net (code "31") (name "SERVO_2") (class "Default")
      (node (ref "P2") (pin "2") (pinfunction "2_2") (pintype "passive"))
      (node (ref "U2") (pin "5") (pinfunction "(OC3A/AIN1)_PE3_5") (pintype "bidirectional"))
    )
    (net (code "32") (name "SERVO_3") (class "Default")
      (node (ref "P3") (pin "2") (pinfunction "2_2") (pintype "passive"))
      (node (ref "U2") (pin "15") (pinfunction "(OC4A)_PH3_15") (pintype "bidirectional"))
    )
    (net (code "33") (name "SERVO_4") (class "Default")
      (node (ref "P5") (pin "2") (pinfunction "2_2") (pintype "passive"))
      (node (ref "U2") (pin "16") (pinfunction "(OC4B)_PH4_16") (pintype "bidirectional"))
    )
    (net (code "34") (name "TCK") (class "Default")
      (node (ref "P10") (pin "6") (pinfunction "6_6") (pintype "passive"))
      (node (ref "U2") (pin "93") (pinfunction "PF4_(ADC4/TCK)_93") (pintype "bidirectional"))
    )
    (net (code "35") (name "TDI") (class "Default")
      (node (ref "P10") (pin "3") (pinfunction "3_3") (pintype "passive"))
      (node (ref "U2") (pin "90") (pinfunction "PF7_(ADC7/TDI)_90") (pintype "bidirectional"))
    )
    (net (code "36") (name "TDO") (class "Default")
      (node (ref "P10") (pin "4") (pinfunction "4_4") (pintype "passive"))
      (node (ref "U2") (pin "91") (pinfunction "PF6_(ADC6/TDO)_91") (pintype "bidirectional"))
    )
    (net (code "37") (name "TMS") (class "Default")
      (node (ref "P10") (pin "5") (pinfunction "5_5") (pintype "passive"))
      (node (ref "U2") (pin "92") (pinfunction "PF5_(ADC5/TMS)_92") (pintype "bidirectional"))
    )
    (net (code "38") (name "TX") (class "Default")
      (node (ref "P13") (pin "3") (pinfunction "3_3") (pintype "passive"))
      (node (ref "U2") (pin "3") (pinfunction "(TXD0)_PE1_3") (pintype "bidirectional"))
    )
    (net (code "39") (name "XTAL1") (class "Default")
      (node (ref "R8") (pin "1") (pinfunction "1_1") (pintype "passive"))
      (node (ref "U2") (pin "34") (pinfunction "XTAL1_34") (pintype "input"))
      (node (ref "Y2") (pin "1") (pinfunction "IN_1") (pintype "passive"))
    )
    (net (code "40") (name "XTAL2") (class "Default")
      (node (ref "R8") (pin "2") (pinfunction "2_2") (pintype "passive"))
      (node (ref "U2") (pin "33") (pinfunction "XTAL2_33") (pintype "output"))
      (node (ref "Y2") (pin "3") (pinfunction "OUT_3") (pintype "passive"))
    )
    (net (code "41") (name "nRESET") (class "Default")
      (node (ref "C11") (pin "1") (pinfunction "1_1") (pintype "passive"))
      (node (ref "P11") (pin "6") (pinfunction "6_6") (pintype "passive"))
      (node (ref "R2") (pin "1") (pinfunction "1_1") (pintype "passive"))
      (node (ref "U2") (pin "30") (pinfunction "~{RESET}_30") (pintype "input"))
    )
    (net (code "42") (name "unconnected-(D1-NOPAD-Pad2)") (class "Default")
      (node (ref "D1") (pin "2") (pinfunction "NOPAD_2") (pintype "passive+no_connect"))
    )
    (net (code "43") (name "unconnected-(U2-(CLKO{slash}ICP3{slash}INT7)_PE7-Pad9)") (class "Default")
      (node (ref "U2") (pin "9") (pinfunction "(CLKO/ICP3/INT7)_PE7_9") (pintype "bidirectional"))
    )
    (net (code "44") (name "unconnected-(U2-(ICP1)_PD4-Pad47)") (class "Default")
      (node (ref "U2") (pin "47") (pinfunction "(ICP1)_PD4_47") (pintype "bidirectional"))
    )
    (net (code "45") (name "unconnected-(U2-(ICP4)_PL0-Pad35)") (class "Default")
      (node (ref "U2") (pin "35") (pinfunction "(ICP4)_PL0_35") (pintype "bidirectional"))
    )
    (net (code "46") (name "unconnected-(U2-(ICP5)_PL1-Pad36)") (class "Default")
      (node (ref "U2") (pin "36") (pinfunction "(ICP5)_PL1_36") (pintype "bidirectional"))
    )
    (net (code "47") (name "unconnected-(U2-(OC0A{slash}OC1C{slash}PCINT7)_PB7-Pad26)") (class "Default")
      (node (ref "U2") (pin "26") (pinfunction "(OC0A/OC1C/PCINT7)_PB7_26") (pintype "bidirectional"))
    )
    (net (code "48") (name "unconnected-(U2-(OC1A{slash}PCINT5)_PB5-Pad24)") (class "Default")
      (node (ref "U2") (pin "24") (pinfunction "(OC1A/PCINT5)_PB5_24") (pintype "bidirectional"))
    )
    (net (code "49") (name "unconnected-(U2-(OC1B{slash}PCINT6)_PB6-Pad25)") (class "Default")
      (node (ref "U2") (pin "25") (pinfunction "(OC1B/PCINT6)_PB6_25") (pintype "bidirectional"))
    )
    (net (code "50") (name "unconnected-(U2-(OC2A{slash}PCINT4)_PB4-Pad23)") (class "Default")
      (node (ref "U2") (pin "23") (pinfunction "(OC2A/PCINT4)_PB4_23") (pintype "bidirectional"))
    )
    (net (code "51") (name "unconnected-(U2-(OC2B)_PH6-Pad18)") (class "Default")
      (node (ref "U2") (pin "18") (pinfunction "(OC2B)_PH6_18") (pintype "bidirectional"))
    )
    (net (code "52") (name "unconnected-(U2-(OC3B{slash}INT4)_PE4-Pad6)") (class "Default")
      (node (ref "U2") (pin "6") (pinfunction "(OC3B/INT4)_PE4_6") (pintype "bidirectional"))
    )
    (net (code "53") (name "unconnected-(U2-(OC3C{slash}INT5)_PE5-Pad7)") (class "Default")
      (node (ref "U2") (pin "7") (pinfunction "(OC3C/INT5)_PE5_7") (pintype "bidirectional"))
    )
    (net (code "54") (name "unconnected-(U2-(OC4C)_PH5-Pad17)") (class "Default")
      (node (ref "U2") (pin "17") (pinfunction "(OC4C)_PH5_17") (pintype "bidirectional"))
    )
    (net (code "55") (name "unconnected-(U2-(OC5A)_PL3-Pad38)") (class "Default")
      (node (ref "U2") (pin "38") (pinfunction "(OC5A)_PL3_38") (pintype "bidirectional"))
    )
    (net (code "56") (name "unconnected-(U2-(OC5B)_PL4-Pad39)") (class "Default")
      (node (ref "U2") (pin "39") (pinfunction "(OC5B)_PL4_39") (pintype "bidirectional"))
    )
    (net (code "57") (name "unconnected-(U2-(RXD2)_PH0-Pad12)") (class "Default")
      (node (ref "U2") (pin "12") (pinfunction "(RXD2)_PH0_12") (pintype "bidirectional"))
    )
    (net (code "58") (name "unconnected-(U2-(SCL{slash}INT0)_PD0-Pad43)") (class "Default")
      (node (ref "U2") (pin "43") (pinfunction "(SCL/INT0)_PD0_43") (pintype "bidirectional"))
    )
    (net (code "59") (name "unconnected-(U2-(SDA{slash}INT1)_PD1-Pad44)") (class "Default")
      (node (ref "U2") (pin "44") (pinfunction "(SDA/INT1)_PD1_44") (pintype "bidirectional"))
    )
    (net (code "60") (name "unconnected-(U2-(T0)_PD7-Pad50)") (class "Default")
      (node (ref "U2") (pin "50") (pinfunction "(T0)_PD7_50") (pintype "bidirectional"))
    )
    (net (code "61") (name "unconnected-(U2-(T1)_PD6-Pad49)") (class "Default")
      (node (ref "U2") (pin "49") (pinfunction "(T1)_PD6_49") (pintype "bidirectional"))
    )
    (net (code "62") (name "unconnected-(U2-(T3{slash}INT6)_PE6-Pad8)") (class "Default")
      (node (ref "U2") (pin "8") (pinfunction "(T3/INT6)_PE6_8") (pintype "bidirectional"))
    )
    (net (code "63") (name "unconnected-(U2-(T4)_PH7-Pad27)") (class "Default")
      (node (ref "U2") (pin "27") (pinfunction "(T4)_PH7_27") (pintype "bidirectional"))
    )
    (net (code "64") (name "unconnected-(U2-(T5)_PL2-Pad37)") (class "Default")
      (node (ref "U2") (pin "37") (pinfunction "(T5)_PL2_37") (pintype "bidirectional"))
    )
    (net (code "65") (name "unconnected-(U2-(TOSC1)_PG4-Pad29)") (class "Default")
      (node (ref "U2") (pin "29") (pinfunction "(TOSC1)_PG4_29") (pintype "bidirectional"))
    )
    (net (code "66") (name "unconnected-(U2-(TOSC2)_PG3-Pad28)") (class "Default")
      (node (ref "U2") (pin "28") (pinfunction "(TOSC2)_PG3_28") (pintype "bidirectional"))
    )
    (net (code "67") (name "unconnected-(U2-(TXD1{slash}INT3)_PD3-Pad46)") (class "Default")
      (node (ref "U2") (pin "46") (pinfunction "(TXD1/INT3)_PD3_46") (pintype "bidirectional"))
    )
    (net (code "68") (name "unconnected-(U2-(TXD2)_PH1-Pad13)") (class "Default")
      (node (ref "U2") (pin "13") (pinfunction "(TXD2)_PH1_13") (pintype "bidirectional"))
    )
    (net (code "69") (name "unconnected-(U2-(XCK0{slash}AIN0)_PE2-Pad4)") (class "Default")
      (node (ref "U2") (pin "4") (pinfunction "(XCK0/AIN0)_PE2_4") (pintype "bidirectional"))
    )
    (net (code "70") (name "unconnected-(U2-(XCK1)_PD5-Pad48)") (class "Default")
      (node (ref "U2") (pin "48") (pinfunction "(XCK1)_PD5_48") (pintype "bidirectional"))
    )
    (net (code "71") (name "unconnected-(U2-(XCK2)_PH2-Pad14)") (class "Default")
      (node (ref "U2") (pin "14") (pinfunction "(XCK2)_PH2_14") (pintype "bidirectional"))
    )
    (net (code "72") (name "unconnected-(U2-OC5C)_PL5-Pad40)") (class "Default")
      (node (ref "U2") (pin "40") (pinfunction "OC5C)_PL5_40") (pintype "bidirectional"))
    )
    (net (code "73") (name "unconnected-(U2-PA4_(AD4)-Pad74)") (class "Default")
      (node (ref "U2") (pin "74") (pinfunction "PA4_(AD4)_74") (pintype "bidirectional"))
    )
    (net (code "74") (name "unconnected-(U2-PA5_(AD5)-Pad73)") (class "Default")
      (node (ref "U2") (pin "73") (pinfunction "PA5_(AD5)_73") (pintype "bidirectional"))
    )
    (net (code "75") (name "unconnected-(U2-PA6_(AD6)-Pad72)") (class "Default")
      (node (ref "U2") (pin "72") (pinfunction "PA6_(AD6)_72") (pintype "bidirectional"))
    )
    (net (code "76") (name "unconnected-(U2-PA7_(AD7)-Pad71)") (class "Default")
      (node (ref "U2") (pin "71") (pinfunction "PA7_(AD7)_71") (pintype "bidirectional"))
    )
    (net (code "77") (name "unconnected-(U2-PC0_(A8)-Pad53)") (class "Default")
      (node (ref "U2") (pin "53") (pinfunction "PC0_(A8)_53") (pintype "bidirectional"))
    )
    (net (code "78") (name "unconnected-(U2-PC1_(A9)-Pad54)") (class "Default")
      (node (ref "U2") (pin "54") (pinfunction "PC1_(A9)_54") (pintype "bidirectional"))
    )
    (net (code "79") (name "unconnected-(U2-PC2_(A10)-Pad55)") (class "Default")
      (node (ref "U2") (pin "55") (pinfunction "PC2_(A10)_55") (pintype "bidirectional"))
    )
    (net (code "80") (name "unconnected-(U2-PC3_(A11)-Pad56)") (class "Default")
      (node (ref "U2") (pin "56") (pinfunction "PC3_(A11)_56") (pintype "bidirectional"))
    )
    (net (code "81") (name "unconnected-(U2-PC4_(A12)-Pad57)") (class "Default")
      (node (ref "U2") (pin "57") (pinfunction "PC4_(A12)_57") (pintype "bidirectional"))
    )
    (net (code "82") (name "unconnected-(U2-PC5_(A13)-Pad58)") (class "Default")
      (node (ref "U2") (pin "58") (pinfunction "PC5_(A13)_58") (pintype "bidirectional"))
    )
    (net (code "83") (name "unconnected-(U2-PC6_(A14)-Pad59)") (class "Default")
      (node (ref "U2") (pin "59") (pinfunction "PC6_(A14)_59") (pintype "bidirectional"))
    )
    (net (code "84") (name "unconnected-(U2-PC7_(A15)-Pad60)") (class "Default")
      (node (ref "U2") (pin "60") (pinfunction "PC7_(A15)_60") (pintype "bidirectional"))
    )
    (net (code "85") (name "unconnected-(U2-PF0_(ADC0)-Pad97)") (class "Default")
      (node (ref "U2") (pin "97") (pinfunction "PF0_(ADC0)_97") (pintype "bidirectional"))
    )
    (net (code "86") (name "unconnected-(U2-PF1_(ADC1)-Pad96)") (class "Default")
      (node (ref "U2") (pin "96") (pinfunction "PF1_(ADC1)_96") (pintype "bidirectional"))
    )
    (net (code "87") (name "unconnected-(U2-PF2_(ADC2)-Pad95)") (class "Default")
      (node (ref "U2") (pin "95") (pinfunction "PF2_(ADC2)_95") (pintype "bidirectional"))
    )
    (net (code "88") (name "unconnected-(U2-PF3_(ADC3)-Pad94)") (class "Default")
      (node (ref "U2") (pin "94") (pinfunction "PF3_(ADC3)_94") (pintype "bidirectional"))
    )
    (net (code "89") (name "unconnected-(U2-PG0_(~WR)-Pad51)") (class "Default")
      (node (ref "U2") (pin "51") (pinfunction "PG0_(~WR)_51") (pintype "bidirectional"))
    )
    (net (code "90") (name "unconnected-(U2-PG1_(~RD)-Pad52)") (class "Default")
      (node (ref "U2") (pin "52") (pinfunction "PG1_(~RD)_52") (pintype "bidirectional"))
    )
    (net (code "91") (name "unconnected-(U2-PG2_(ALE)-Pad70)") (class "Default")
      (node (ref "U2") (pin "70") (pinfunction "PG2_(ALE)_70") (pintype "bidirectional"))
    )
    (net (code "92") (name "unconnected-(U2-PJ0_(RXD3{slash}PCINT9)-Pad63)") (class "Default")
      (node (ref "U2") (pin "63") (pinfunction "PJ0_(RXD3/PCINT9)_63") (pintype "bidirectional"))
    )
    (net (code "93") (name "unconnected-(U2-PJ1_(TXD3{slash}PCINT10)-Pad64)") (class "Default")
      (node (ref "U2") (pin "64") (pinfunction "PJ1_(TXD3/PCINT10)_64") (pintype "bidirectional"))
    )
    (net (code "94") (name "unconnected-(U2-PJ2_(XCK3{slash}PCINT11)-Pad65)") (class "Default")
      (node (ref "U2") (pin "65") (pinfunction "PJ2_(XCK3/PCINT11)_65") (pintype "bidirectional"))
    )
    (net (code "95") (name "unconnected-(U2-PJ3_(PCINT12)-Pad66)") (class "Default")
      (node (ref "U2") (pin "66") (pinfunction "PJ3_(PCINT12)_66") (pintype "bidirectional"))
    )
    (net (code "96") (name "unconnected-(U2-PJ4_(PCINT13)-Pad67)") (class "Default")
      (node (ref "U2") (pin "67") (pinfunction "PJ4_(PCINT13)_67") (pintype "bidirectional"))
    )
    (net (code "97") (name "unconnected-(U2-PJ5_(PCINT14)-Pad68)") (class "Default")
      (node (ref "U2") (pin "68") (pinfunction "PJ5_(PCINT14)_68") (pintype "bidirectional"))
    )
    (net (code "98") (name "unconnected-(U2-PJ6_(PCINT15)-Pad69)") (class "Default")
      (node (ref "U2") (pin "69") (pinfunction "PJ6_(PCINT15)_69") (pintype "bidirectional"))
    )
    (net (code "99") (name "unconnected-(U2-PJ7-Pad79)") (class "Default")
      (node (ref "U2") (pin "79") (pinfunction "PJ7_79") (pintype "bidirectional"))
    )
    (net (code "100") (name "unconnected-(U2-PK0_(ADC8{slash}PCINT16)-Pad89)") (class "Default")
      (node (ref "U2") (pin "89") (pinfunction "PK0_(ADC8/PCINT16)_89") (pintype "bidirectional"))
    )
    (net (code "101") (name "unconnected-(U2-PK1_(ADC9{slash}PCINT17)-Pad88)") (class "Default")
      (node (ref "U2") (pin "88") (pinfunction "PK1_(ADC9/PCINT17)_88") (pintype "bidirectional"))
    )
    (net (code "102") (name "unconnected-(U2-PK2_(ADC10{slash}PCINT18)-Pad87)") (class "Default")
      (node (ref "U2") (pin "87") (pinfunction "PK2_(ADC10/PCINT18)_87") (pintype "bidirectional"))
    )
    (net (code "103") (name "unconnected-(U2-PK3_(ADC11{slash}PCINT19)-Pad86)") (class "Default")
      (node (ref "U2") (pin "86") (pinfunction "PK3_(ADC11/PCINT19)_86") (pintype "bidirectional"))
    )
    (net (code "104") (name "unconnected-(U2-PK4_(ADC12{slash}PCINT20)-Pad85)") (class "Default")
      (node (ref "U2") (pin "85") (pinfunction "PK4_(ADC12/PCINT20)_85") (pintype "bidirectional"))
    )
    (net (code "105") (name "unconnected-(U2-PK5_(ADC13{slash}PCINT21)-Pad84)") (class "Default")
      (node (ref "U2") (pin "84") (pinfunction "PK5_(ADC13/PCINT21)_84") (pintype "bidirectional"))
    )
    (net (code "106") (name "unconnected-(U2-PK6_(ADC14{slash}PCINT22)-Pad83)") (class "Default")
      (node (ref "U2") (pin "83") (pinfunction "PK6_(ADC14/PCINT22)_83") (pintype "bidirectional"))
    )
    (net (code "107") (name "unconnected-(U2-PK7_(ADC15{slash}PCINT23)-Pad82)") (class "Default")
      (node (ref "U2") (pin "82") (pinfunction "PK7_(ADC15/PCINT23)_82") (pintype "bidirectional"))
    )
    (net (code "108") (name "unconnected-(U2-PL6-Pad41)") (class "Default")
      (node (ref "U2") (pin "41") (pinfunction "PL6_41") (pintype "bidirectional"))
    )
    (net (code "109") (name "unconnected-(U2-PL7-Pad42)") (class "Default")
      (node (ref "U2") (pin "42") (pinfunction "PL7_42") (pintype "bidirectional"))
    )
    (net (code "110") (name "unconnected-(U3-SPLIT-Pad5)") (class "Default")
      (node (ref "U3") (pin "5") (pinfunction "SPLIT_5") (pintype "passive+no_connect"))
    )
    (net (code "111") (name "unconnected-(U4-CLKOUT{slash}SOF-Pad3)") (class "Default")
      (node (ref "U4") (pin "3") (pinfunction "CLKOUT/SOF_3") (pintype "passive"))
    )
    (net (code "112") (name "unconnected-(U4-NC-Pad6)") (class "Default")
      (node (ref "U4") (pin "6") (pinfunction "NC_6") (pintype "passive+no_connect"))
    )
    (net (code "113") (name "unconnected-(U4-NC-Pad15)") (class "Default")
      (node (ref "U4") (pin "15") (pinfunction "NC_15") (pintype "passive+no_connect"))
    )
    (net (code "114") (name "unconnected-(U4-RX0BF#-Pad12)") (class "Default")
      (node (ref "U4") (pin "12") (pinfunction "RX0BF#_12") (pintype "passive"))
    )
    (net (code "115") (name "unconnected-(U4-RX1BF#-Pad11)") (class "Default")
      (node (ref "U4") (pin "11") (pinfunction "RX1BF#_11") (pintype "passive"))
    )
    (net (code "116") (name "unconnected-(U4-TX0RTS#-Pad4)") (class "Default")
      (node (ref "U4") (pin "4") (pinfunction "TX0RTS#_4") (pintype "passive"))
    )
    (net (code "117") (name "unconnected-(U4-TX1RTS#-Pad5)") (class "Default")
      (node (ref "U4") (pin "5") (pinfunction "TX1RTS#_5") (pintype "passive"))
    )
    (net (code "118") (name "unconnected-(U4-TX2RTS#-Pad7)") (class "Default")
      (node (ref "U4") (pin "7") (pinfunction "TX2RTS#_7") (pintype "passive"))
    )
  )
)
